# TRC_power1_0_0.net
KiCad netlist of a schematic drawn in EAGLE
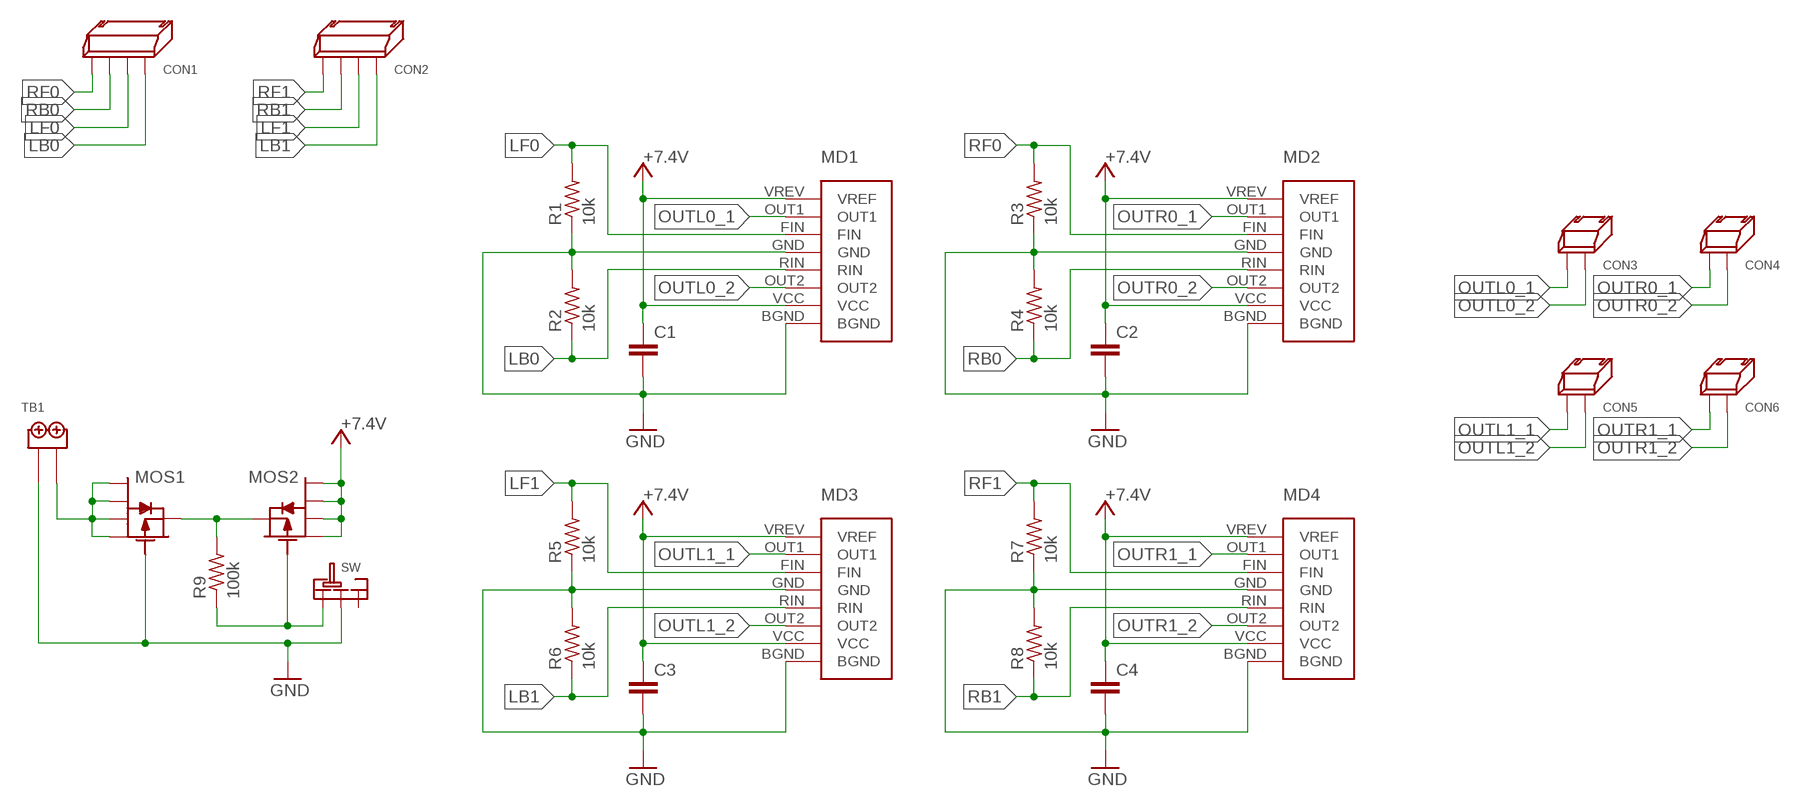
[diagram p0: schematic, sheet 1]

(export (version "E")
  (design (tool "Eeschema 10.0.6"))
  (components
    (comp (ref "C1")
      (value "C-EUC0603")
      (footprint "eagle-import:C0603")
      (libsource (lib "eagle-import") (part "C-EUC0603"))
    )
    (comp (ref "C2")
      (value "C-EUC0603")
      (footprint "eagle-import:C0603")
      (libsource (lib "eagle-import") (part "C-EUC0603"))
    )
    (comp (ref "C3")
      (value "C-EUC0603")
      (footprint "eagle-import:C0603")
      (libsource (lib "eagle-import") (part "C-EUC0603"))
    )
    (comp (ref "C4")
      (value "C-EUC0603")
      (footprint "eagle-import:C0603")
      (libsource (lib "eagle-import") (part "C-EUC0603"))
    )
    (comp (ref "CON1")
      (value "4PIN_SIDE")
      (footprint "eagle-import:4PIN_SIDE")
      (libsource (lib "eagle-import") (part "4PIN_SIDE"))
    )
    (comp (ref "CON2")
      (value "4PIN_SIDE")
      (footprint "eagle-import:4PIN_SIDE")
      (libsource (lib "eagle-import") (part "4PIN_SIDE"))
    )
    (comp (ref "CON3")
      (value "2PIN_SIDE")
      (footprint "eagle-import:2PIN_SIDE")
      (libsource (lib "eagle-import") (part "2PIN_SIDE"))
    )
    (comp (ref "CON4")
      (value "2PIN_SIDE")
      (footprint "eagle-import:2PIN_SIDE")
      (libsource (lib "eagle-import") (part "2PIN_SIDE"))
    )
    (comp (ref "CON5")
      (value "2PIN_SIDE")
      (footprint "eagle-import:2PIN_SIDE")
      (libsource (lib "eagle-import") (part "2PIN_SIDE"))
    )
    (comp (ref "CON6")
      (value "2PIN_SIDE")
      (footprint "eagle-import:2PIN_SIDE")
      (libsource (lib "eagle-import") (part "2PIN_SIDE"))
    )
    (comp (ref "MD1")
      (value "BD6222HFP-TR")
      (footprint "eagle-import:BD6222HFP-TR")
      (libsource (lib "eagle-import") (part "BD6222HFP-TR"))
    )
    (comp (ref "MD2")
      (value "BD6222HFP-TR")
      (footprint "eagle-import:BD6222HFP-TR")
      (libsource (lib "eagle-import") (part "BD6222HFP-TR"))
    )
    (comp (ref "MD3")
      (value "BD6222HFP-TR")
      (footprint "eagle-import:BD6222HFP-TR")
      (libsource (lib "eagle-import") (part "BD6222HFP-TR"))
    )
    (comp (ref "MD4")
      (value "BD6222HFP-TR")
      (footprint "eagle-import:BD6222HFP-TR")
      (libsource (lib "eagle-import") (part "BD6222HFP-TR"))
    )
    (comp (ref "MOS1")
      (value "PCH_SSM6J808R")
      (footprint "eagle-import:SSM6J808R")
      (libsource (lib "eagle-import") (part "PCH_SSM6J808R"))
    )
    (comp (ref "MOS2")
      (value "PCH_SSM6J808R")
      (footprint "eagle-import:SSM6J808R")
      (libsource (lib "eagle-import") (part "PCH_SSM6J808R"))
    )
    (comp (ref "R1")
      (value "10k")
      (footprint "eagle-import:R0603")
      (libsource (lib "eagle-import") (part "R-US_R0603"))
    )
    (comp (ref "R2")
      (value "10k")
      (footprint "eagle-import:R0603")
      (libsource (lib "eagle-import") (part "R-US_R0603"))
    )
    (comp (ref "R3")
      (value "10k")
      (footprint "eagle-import:R0603")
      (libsource (lib "eagle-import") (part "R-US_R0603"))
    )
    (comp (ref "R4")
      (value "10k")
      (footprint "eagle-import:R0603")
      (libsource (lib "eagle-import") (part "R-US_R0603"))
    )
    (comp (ref "R5")
      (value "10k")
      (footprint "eagle-import:R0603")
      (libsource (lib "eagle-import") (part "R-US_R0603"))
    )
    (comp (ref "R6")
      (value "10k")
      (footprint "eagle-import:R0603")
      (libsource (lib "eagle-import") (part "R-US_R0603"))
    )
    (comp (ref "R7")
      (value "10k")
      (footprint "eagle-import:R0603")
      (libsource (lib "eagle-import") (part "R-US_R0603"))
    )
    (comp (ref "R8")
      (value "10k")
      (footprint "eagle-import:R0603")
      (libsource (lib "eagle-import") (part "R-US_R0603"))
    )
    (comp (ref "R9")
      (value "100k")
      (footprint "eagle-import:R0603")
      (libsource (lib "eagle-import") (part "R-US_R0603"))
    )
    (comp (ref "SW")
      (value "SRIDE_SWITCH")
      (footprint "eagle-import:SRIDE_SWITCH")
      (libsource (lib "eagle-import") (part "SRIDE_SWITCH"))
    )
    (comp (ref "TB1")
      (value "2PIN")
      (footprint "eagle-import:2PIN")
      (libsource (lib "eagle-import") (part "2PIN"))
    )
  )
  (nets
    (net (code "1") (name "+7.4V") (class "Default")
      (node (ref "C1") (pin "1") (pinfunction "1_1") (pintype "passive"))
      (node (ref "C2") (pin "1") (pinfunction "1_1") (pintype "passive"))
      (node (ref "C3") (pin "1") (pinfunction "1_1") (pintype "passive"))
      (node (ref "C4") (pin "1") (pinfunction "1_1") (pintype "passive"))
      (node (ref "MD1") (pin "VCC") (pinfunction "VCC_VCC") (pintype "bidirectional"))
      (node (ref "MD1") (pin "VREV") (pinfunction "VREF_VREV") (pintype "bidirectional"))
      (node (ref "MD2") (pin "VCC") (pinfunction "VCC_VCC") (pintype "bidirectional"))
      (node (ref "MD2") (pin "VREV") (pinfunction "VREF_VREV") (pintype "bidirectional"))
      (node (ref "MD3") (pin "VCC") (pinfunction "VCC_VCC") (pintype "bidirectional"))
      (node (ref "MD3") (pin "VREV") (pinfunction "VREF_VREV") (pintype "bidirectional"))
      (node (ref "MD4") (pin "VCC") (pinfunction "VCC_VCC") (pintype "bidirectional"))
      (node (ref "MD4") (pin "VREV") (pinfunction "VREF_VREV") (pintype "bidirectional"))
      (node (ref "MOS2") (pin "1") (pinfunction "1_1") (pintype "bidirectional"))
      (node (ref "MOS2") (pin "2") (pinfunction "2_2") (pintype "bidirectional"))
      (node (ref "MOS2") (pin "5") (pinfunction "5_5") (pintype "bidirectional"))
      (node (ref "MOS2") (pin "6") (pinfunction "6_6") (pintype "bidirectional"))
    )
    (net (code "2") (name "GND") (class "Default")
      (node (ref "C1") (pin "2") (pinfunction "2_2") (pintype "passive"))
      (node (ref "C2") (pin "2") (pinfunction "2_2") (pintype "passive"))
      (node (ref "C3") (pin "2") (pinfunction "2_2") (pintype "passive"))
      (node (ref "C4") (pin "2") (pinfunction "2_2") (pintype "passive"))
      (node (ref "MD1") (pin "BGND") (pinfunction "BGND_BGND") (pintype "bidirectional"))
      (node (ref "MD1") (pin "GND") (pinfunction "GND_GND") (pintype "bidirectional"))
      (node (ref "MD2") (pin "BGND") (pinfunction "BGND_BGND") (pintype "bidirectional"))
      (node (ref "MD2") (pin "GND") (pinfunction "GND_GND") (pintype "bidirectional"))
      (node (ref "MD3") (pin "BGND") (pinfunction "BGND_BGND") (pintype "bidirectional"))
      (node (ref "MD3") (pin "GND") (pinfunction "GND_GND") (pintype "bidirectional"))
      (node (ref "MD4") (pin "BGND") (pinfunction "BGND_BGND") (pintype "bidirectional"))
      (node (ref "MD4") (pin "GND") (pinfunction "GND_GND") (pintype "bidirectional"))
      (node (ref "MOS1") (pin "3") (pinfunction "3_3") (pintype "bidirectional"))
      (node (ref "R1") (pin "1") (pinfunction "1_1") (pintype "passive"))
      (node (ref "R2") (pin "2") (pinfunction "2_2") (pintype "passive"))
      (node (ref "R3") (pin "1") (pinfunction "1_1") (pintype "passive"))
      (node (ref "R4") (pin "2") (pinfunction "2_2") (pintype "passive"))
      (node (ref "R5") (pin "1") (pinfunction "1_1") (pintype "passive"))
      (node (ref "R6") (pin "2") (pinfunction "2_2") (pintype "passive"))
      (node (ref "R7") (pin "1") (pinfunction "1_1") (pintype "passive"))
      (node (ref "R8") (pin "2") (pinfunction "2_2") (pintype "passive"))
      (node (ref "SW") (pin "LR") (pinfunction "LR_LR") (pintype "bidirectional"))
      (node (ref "TB1") (pin "P$1") (pinfunction "P$1_P$1") (pintype "bidirectional"))
    )
    (net (code "3") (name "LB0") (class "Default")
      (node (ref "CON1") (pin "P$4") (pinfunction "P$4_P$4") (pintype "bidirectional"))
      (node (ref "MD1") (pin "RIN") (pinfunction "RIN_RIN") (pintype "bidirectional"))
      (node (ref "R2") (pin "1") (pinfunction "1_1") (pintype "passive"))
    )
    (net (code "4") (name "LB1") (class "Default")
      (node (ref "CON2") (pin "P$4") (pinfunction "P$4_P$4") (pintype "bidirectional"))
      (node (ref "MD3") (pin "RIN") (pinfunction "RIN_RIN") (pintype "bidirectional"))
      (node (ref "R6") (pin "1") (pinfunction "1_1") (pintype "passive"))
    )
    (net (code "5") (name "LF0") (class "Default")
      (node (ref "CON1") (pin "P$3") (pinfunction "P$3_P$3") (pintype "bidirectional"))
      (node (ref "MD1") (pin "FIN") (pinfunction "FIN_FIN") (pintype "bidirectional"))
      (node (ref "R1") (pin "2") (pinfunction "2_2") (pintype "passive"))
    )
    (net (code "6") (name "LF1") (class "Default")
      (node (ref "CON2") (pin "P$3") (pinfunction "P$3_P$3") (pintype "bidirectional"))
      (node (ref "MD3") (pin "FIN") (pinfunction "FIN_FIN") (pintype "bidirectional"))
      (node (ref "R5") (pin "2") (pinfunction "2_2") (pintype "passive"))
    )
    (net (code "7") (name "Net-(MOS1-Pad1)") (class "Default")
      (node (ref "MOS1") (pin "1") (pinfunction "1_1") (pintype "bidirectional"))
      (node (ref "MOS1") (pin "2") (pinfunction "2_2") (pintype "bidirectional"))
      (node (ref "MOS1") (pin "5") (pinfunction "5_5") (pintype "bidirectional"))
      (node (ref "MOS1") (pin "6") (pinfunction "6_6") (pintype "bidirectional"))
      (node (ref "TB1") (pin "P$2") (pinfunction "P$2_P$2") (pintype "bidirectional"))
    )
    (net (code "8") (name "Net-(MOS1-Pad4)") (class "Default")
      (node (ref "MOS1") (pin "4") (pinfunction "4_4") (pintype "bidirectional"))
      (node (ref "MOS2") (pin "4") (pinfunction "4_4") (pintype "bidirectional"))
      (node (ref "R9") (pin "2") (pinfunction "2_2") (pintype "passive"))
    )
    (net (code "9") (name "Net-(MOS2-Pad3)") (class "Default")
      (node (ref "MOS2") (pin "3") (pinfunction "3_3") (pintype "bidirectional"))
      (node (ref "R9") (pin "1") (pinfunction "1_1") (pintype "passive"))
      (node (ref "SW") (pin "L") (pinfunction "L_L") (pintype "bidirectional"))
    )
    (net (code "10") (name "OUTL0_1") (class "Default")
      (node (ref "CON3") (pin "P$2") (pinfunction "P$2_P$2") (pintype "bidirectional"))
      (node (ref "MD1") (pin "OUT1") (pinfunction "OUT1_OUT1") (pintype "bidirectional"))
    )
    (net (code "11") (name "OUTL0_2") (class "Default")
      (node (ref "CON3") (pin "P$1") (pinfunction "P$1_P$1") (pintype "bidirectional"))
      (node (ref "MD1") (pin "OUT2") (pinfunction "OUT2_OUT2") (pintype "bidirectional"))
    )
    (net (code "12") (name "OUTL1_1") (class "Default")
      (node (ref "CON5") (pin "P$2") (pinfunction "P$2_P$2") (pintype "bidirectional"))
      (node (ref "MD3") (pin "OUT1") (pinfunction "OUT1_OUT1") (pintype "bidirectional"))
    )
    (net (code "13") (name "OUTL1_2") (class "Default")
      (node (ref "CON5") (pin "P$1") (pinfunction "P$1_P$1") (pintype "bidirectional"))
      (node (ref "MD3") (pin "OUT2") (pinfunction "OUT2_OUT2") (pintype "bidirectional"))
    )
    (net (code "14") (name "OUTR0_1") (class "Default")
      (node (ref "CON4") (pin "P$2") (pinfunction "P$2_P$2") (pintype "bidirectional"))
      (node (ref "MD2") (pin "OUT1") (pinfunction "OUT1_OUT1") (pintype "bidirectional"))
    )
    (net (code "15") (name "OUTR0_2") (class "Default")
      (node (ref "CON4") (pin "P$1") (pinfunction "P$1_P$1") (pintype "bidirectional"))
      (node (ref "MD2") (pin "OUT2") (pinfunction "OUT2_OUT2") (pintype "bidirectional"))
    )
    (net (code "16") (name "OUTR1_1") (class "Default")
      (node (ref "CON6") (pin "P$2") (pinfunction "P$2_P$2") (pintype "bidirectional"))
      (node (ref "MD4") (pin "OUT1") (pinfunction "OUT1_OUT1") (pintype "bidirectional"))
    )
    (net (code "17") (name "OUTR1_2") (class "Default")
      (node (ref "CON6") (pin "P$1") (pinfunction "P$1_P$1") (pintype "bidirectional"))
      (node (ref "MD4") (pin "OUT2") (pinfunction "OUT2_OUT2") (pintype "bidirectional"))
    )
    (net (code "18") (name "RB0") (class "Default")
      (node (ref "CON1") (pin "P$1") (pinfunction "P$1_P$1") (pintype "bidirectional"))
      (node (ref "MD2") (pin "RIN") (pinfunction "RIN_RIN") (pintype "bidirectional"))
      (node (ref "R4") (pin "1") (pinfunction "1_1") (pintype "passive"))
    )
    (net (code "19") (name "RB1") (class "Default")
      (node (ref "CON2") (pin "P$1") (pinfunction "P$1_P$1") (pintype "bidirectional"))
      (node (ref "MD4") (pin "RIN") (pinfunction "RIN_RIN") (pintype "bidirectional"))
      (node (ref "R8") (pin "1") (pinfunction "1_1") (pintype "passive"))
    )
    (net (code "20") (name "RF0") (class "Default")
      (node (ref "CON1") (pin "P$2") (pinfunction "P$2_P$2") (pintype "bidirectional"))
      (node (ref "MD2") (pin "FIN") (pinfunction "FIN_FIN") (pintype "bidirectional"))
      (node (ref "R3") (pin "2") (pinfunction "2_2") (pintype "passive"))
    )
    (net (code "21") (name "RF1") (class "Default")
      (node (ref "CON2") (pin "P$2") (pinfunction "P$2_P$2") (pintype "bidirectional"))
      (node (ref "MD4") (pin "FIN") (pinfunction "FIN_FIN") (pintype "bidirectional"))
      (node (ref "R7") (pin "2") (pinfunction "2_2") (pintype "passive"))
    )
    (net (code "22") (name "unconnected-(SW-PadR)") (class "Default")
      (node (ref "SW") (pin "R") (pinfunction "R_R") (pintype "bidirectional"))
    )
  )
)
